# STM32_Motherboard.net
KiCad netlist of a schematic drawn in Altium Designer
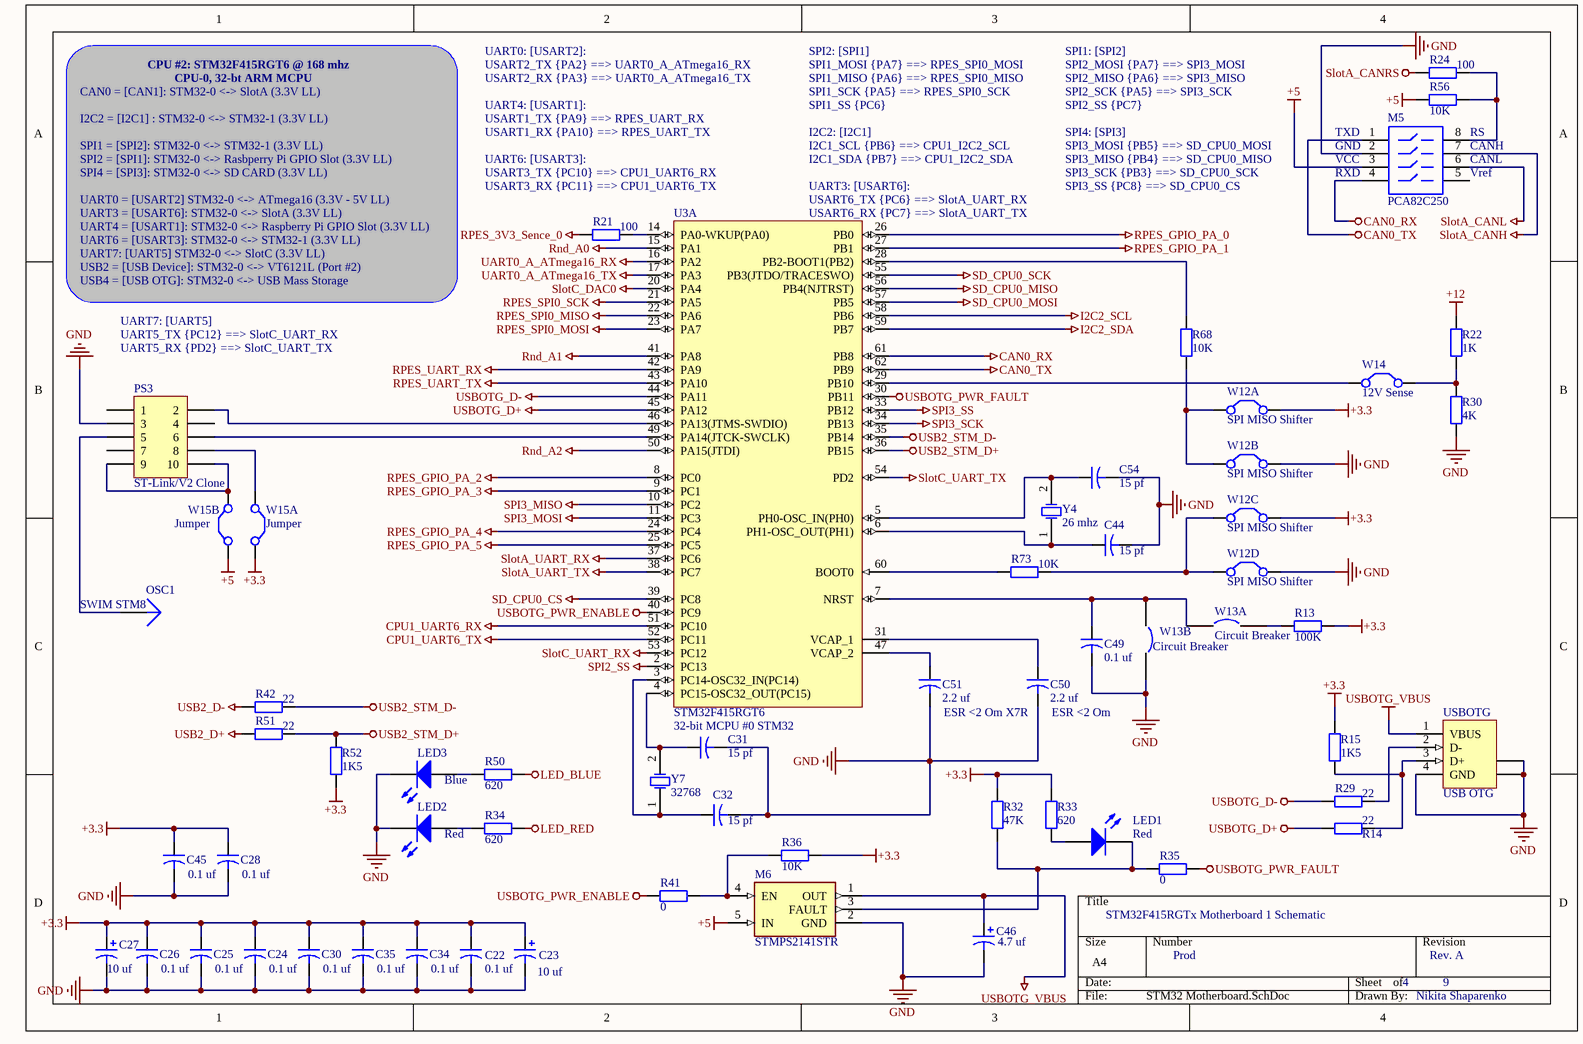
[diagram p0: STM32 Motherboard.SchDoc]

(export (version "E")
  (design (tool "Eeschema 10.0.6"))
  (components
    (comp (ref "C22")
      (value "0.1 uf")
      (footprint "CAPR5-4X5")
      (description "Capacitor")
      (fields (field (name "Comment") "Cap2") (field (name "PUBLISHER") "Altium Limited"))
      (libsource (lib "Miscellaneous Devices") (part "Cap2"))
    )
    (comp (ref "C23")
      (value "10 uf")
      (footprint "RAD-0.2")
      (description "Polarized Capacitor (Radial)")
      (fields (field (name "Comment") "Cap Pol1") (field (name "PUBLISHER") "Altium Limited"))
      (libsource (lib "Miscellaneous Devices") (part "Cap Pol1"))
    )
    (comp (ref "C24")
      (value "0.1 uf")
      (footprint "CAPR5-4X5")
      (description "Capacitor")
      (fields (field (name "Comment") "Cap2") (field (name "PUBLISHER") "Altium Limited"))
      (libsource (lib "Miscellaneous Devices") (part "Cap2"))
    )
    (comp (ref "C25")
      (value "0.1 uf")
      (footprint "CAPR5-4X5")
      (description "Capacitor")
      (fields (field (name "Comment") "Cap2") (field (name "PUBLISHER") "Altium Limited"))
      (libsource (lib "Miscellaneous Devices") (part "Cap2"))
    )
    (comp (ref "C26")
      (value "0.1 uf")
      (footprint "CAPR5-4X5")
      (description "Capacitor")
      (fields (field (name "Comment") "Cap2") (field (name "PUBLISHER") "Altium Limited"))
      (libsource (lib "Miscellaneous Devices") (part "Cap2"))
    )
    (comp (ref "C27")
      (value "10 uf")
      (footprint "RAD-0.2")
      (description "Polarized Capacitor (Radial)")
      (fields (field (name "Comment") "Cap Pol1") (field (name "PUBLISHER") "Altium Limited"))
      (libsource (lib "Miscellaneous Devices") (part "Cap Pol1"))
    )
    (comp (ref "C28")
      (value "0.1 uf")
      (footprint "CAPR5-4X5")
      (description "Capacitor")
      (fields (field (name "Comment") "Cap2") (field (name "PUBLISHER") "Altium Limited"))
      (libsource (lib "Miscellaneous Devices") (part "Cap2"))
    )
    (comp (ref "C30")
      (value "0.1 uf")
      (footprint "CAPR5-4X5")
      (description "Capacitor")
      (fields (field (name "Comment") "Cap2") (field (name "PUBLISHER") "Altium Limited"))
      (libsource (lib "Miscellaneous Devices") (part "Cap2"))
    )
    (comp (ref "C31")
      (value "15 pf")
      (footprint "CAPR5-4X5")
      (description "Capacitor")
      (fields (field (name "Comment") "Cap2") (field (name "PUBLISHER") "Altium Limited"))
      (libsource (lib "Miscellaneous Devices") (part "Cap2"))
    )
    (comp (ref "C32")
      (value "15 pf")
      (footprint "CAPR5-4X5")
      (description "Capacitor")
      (fields (field (name "Comment") "Cap2") (field (name "PUBLISHER") "Altium Limited"))
      (libsource (lib "Miscellaneous Devices") (part "Cap2"))
    )
    (comp (ref "C34")
      (value "0.1 uf")
      (footprint "CAPR5-4X5")
      (description "Capacitor")
      (fields (field (name "Comment") "Cap2") (field (name "PUBLISHER") "Altium Limited"))
      (libsource (lib "Miscellaneous Devices") (part "Cap2"))
    )
    (comp (ref "C35")
      (value "0.1 uf")
      (footprint "CAPR5-4X5")
      (description "Capacitor")
      (fields (field (name "Comment") "Cap2") (field (name "PUBLISHER") "Altium Limited"))
      (libsource (lib "Miscellaneous Devices") (part "Cap2"))
    )
    (comp (ref "C44")
      (value "15 pf")
      (footprint "CAPR5-4X5")
      (description "Capacitor")
      (fields (field (name "Comment") "Cap2") (field (name "PUBLISHER") "Altium Limited"))
      (libsource (lib "Miscellaneous Devices") (part "Cap2"))
    )
    (comp (ref "C45")
      (value "0.1 uf")
      (footprint "CAPR5-4X5")
      (description "Capacitor")
      (fields (field (name "Comment") "Cap2") (field (name "PUBLISHER") "Altium Limited"))
      (libsource (lib "Miscellaneous Devices") (part "Cap2"))
    )
    (comp (ref "C46")
      (value "4.7 uf")
      (footprint "RAD-0.2")
      (description "Polarized Capacitor (Radial)")
      (fields (field (name "Comment") "Cap Pol1") (field (name "PUBLISHER") "Altium Limited"))
      (libsource (lib "Miscellaneous Devices") (part "Cap Pol1"))
    )
    (comp (ref "C49")
      (value "0.1 uf")
      (footprint "CAPR5-4X5")
      (description "Capacitor")
      (fields (field (name "Comment") "Cap2") (field (name "PUBLISHER") "Altium Limited"))
      (libsource (lib "Miscellaneous Devices") (part "Cap2"))
    )
    (comp (ref "C50")
      (value "ESR <2 Om")
      (footprint "CAPR5-4X5")
      (description "Capacitor")
      (fields (field (name "ALTIUM_VALUE") "2.2 uf") (field (name "PUBLISHER") "Altium Limited"))
      (libsource (lib "Miscellaneous Devices") (part "Cap2"))
    )
    (comp (ref "C51")
      (value "ESR <2 Om X7R")
      (footprint "CAPR5-4X5")
      (description "Capacitor")
      (fields (field (name "ALTIUM_VALUE") "2.2 uf") (field (name "PUBLISHER") "Altium Limited"))
      (libsource (lib "Miscellaneous Devices") (part "Cap2"))
    )
    (comp (ref "C54")
      (value "15 pf")
      (footprint "CAPR5-4X5")
      (description "Capacitor")
      (fields (field (name "Comment") "Cap2") (field (name "PUBLISHER") "Altium Limited"))
      (libsource (lib "Miscellaneous Devices") (part "Cap2"))
    )
    (comp (ref "LED1")
      (value "Red")
      (footprint "LED-1")
      (description "Typical RED GaAs LED")
      (fields (field (name "PUBLISHER") "Altium Limited"))
      (libsource (lib "Miscellaneous Devices") (part "LED1"))
    )
    (comp (ref "LED2")
      (value "Red")
      (footprint "LED-1")
      (description "Typical RED GaAs LED")
      (fields (field (name "PUBLISHER") "Altium Limited"))
      (libsource (lib "Miscellaneous Devices") (part "LED1"))
    )
    (comp (ref "LED3")
      (value "Blue")
      (footprint "LED-1")
      (description "Typical RED GaAs LED")
      (fields (field (name "PUBLISHER") "Altium Limited"))
      (libsource (lib "Miscellaneous Devices") (part "LED1"))
    )
    (comp (ref "M5")
      (value "PCA82C250")
      (footprint "8S1_N")
      (description "DIP Switch")
      (fields (field (name "PUBLISHER") "Altium Limited"))
      (libsource (lib "Miscellaneous Devices") (part "SW-DIP4"))
    )
    (comp (ref "M6")
      (value "STMPS2141STR")
      (footprint "SOT95P280X145-5N")
      (description "Power Switch/Driver 1:1 N-Channel 500mA SOT-23-5")
      (fields (field (name "MF") "STMicroelectronics"))
      (libsource (lib "STMPS2141STR") (part "STMPS2141STR"))
    )
    (comp (ref "OSC1")
      (value "SWIM STM8")
      (footprint "PIN1")
      (description "Plug")
      (fields (field (name "PUBLISHER") "Altium Limited"))
      (libsource (lib "Miscellaneous Connectors") (part "Plug"))
    )
    (comp (ref "PS3")
      (value "ST-Link/V2 Clone")
      (footprint "HDR2X5")
      (description "Header, 5-Pin, Dual row")
      (fields (field (name "PUBLISHER") "Altium Limited"))
      (libsource (lib "Miscellaneous Connectors") (part "Header 5X2"))
    )
    (comp (ref "R13")
      (value "100K")
      (footprint "AXIAL-0.4")
      (description "Resistor")
      (fields (field (name "Comment") "Res2") (field (name "PUBLISHER") "Altium Limited"))
      (libsource (lib "") (part "Res2_2"))
    )
    (comp (ref "R14")
      (value "22")
      (footprint "AXIAL-0.4")
      (description "Resistor")
      (fields (field (name "Comment") "Res2") (field (name "PUBLISHER") "Altium Limited"))
      (libsource (lib "Miscellaneous Devices") (part "Res2"))
    )
    (comp (ref "R15")
      (value "1K5")
      (footprint "AXIAL-0.4")
      (description "Resistor")
      (fields (field (name "Comment") "Res2") (field (name "PUBLISHER") "Altium Limited"))
      (libsource (lib "") (part "Res2_1"))
    )
    (comp (ref "R21")
      (value "100")
      (footprint "AXIAL-0.4")
      (description "Resistor")
      (fields (field (name "Comment") "Res2") (field (name "PUBLISHER") "Altium Limited"))
      (libsource (lib "Miscellaneous Devices") (part "Res2"))
    )
    (comp (ref "R22")
      (value "1K")
      (footprint "AXIAL-0.4")
      (description "Resistor")
      (fields (field (name "Comment") "Res2") (field (name "PUBLISHER") "Altium Limited"))
      (libsource (lib "") (part "Res2_1"))
    )
    (comp (ref "R24")
      (value "100")
      (footprint "AXIAL-0.4")
      (description "Resistor")
      (fields (field (name "Comment") "Res2") (field (name "PUBLISHER") "Altium Limited"))
      (libsource (lib "Miscellaneous Devices") (part "Res2"))
    )
    (comp (ref "R29")
      (value "22")
      (footprint "AXIAL-0.4")
      (description "Resistor")
      (fields (field (name "Comment") "Res2") (field (name "PUBLISHER") "Altium Limited"))
      (libsource (lib "Miscellaneous Devices") (part "Res2"))
    )
    (comp (ref "R30")
      (value "4K")
      (footprint "AXIAL-0.4")
      (description "Resistor")
      (fields (field (name "Comment") "Res2") (field (name "PUBLISHER") "Altium Limited"))
      (libsource (lib "") (part "Res2_1"))
    )
    (comp (ref "R32")
      (value "47K")
      (footprint "AXIAL-0.4")
      (description "Resistor")
      (fields (field (name "Comment") "Res2") (field (name "PUBLISHER") "Altium Limited"))
      (libsource (lib "") (part "Res2_1"))
    )
    (comp (ref "R33")
      (value "620")
      (footprint "AXIAL-0.4")
      (description "Resistor")
      (fields (field (name "Comment") "Res2") (field (name "PUBLISHER") "Altium Limited"))
      (libsource (lib "") (part "Res2_1"))
    )
    (comp (ref "R34")
      (value "620")
      (footprint "AXIAL-0.4")
      (description "Resistor")
      (fields (field (name "Comment") "Res2") (field (name "PUBLISHER") "Altium Limited"))
      (libsource (lib "Miscellaneous Devices") (part "Res2"))
    )
    (comp (ref "R35")
      (value "0")
      (footprint "AXIAL-0.4")
      (description "Resistor")
      (fields (field (name "Comment") "Res2") (field (name "PUBLISHER") "Altium Limited"))
      (libsource (lib "Miscellaneous Devices") (part "Res2"))
    )
    (comp (ref "R36")
      (value "10K")
      (footprint "AXIAL-0.4")
      (description "Resistor")
      (fields (field (name "Comment") "Res2") (field (name "PUBLISHER") "Altium Limited"))
      (libsource (lib "") (part "Res2_2"))
    )
    (comp (ref "R41")
      (value "0")
      (footprint "AXIAL-0.4")
      (description "Resistor")
      (fields (field (name "Comment") "Res2") (field (name "PUBLISHER") "Altium Limited"))
      (libsource (lib "") (part "Res2_2"))
    )
    (comp (ref "R42")
      (value "22")
      (footprint "AXIAL-0.4")
      (description "Resistor")
      (fields (field (name "Comment") "Res2") (field (name "PUBLISHER") "Altium Limited"))
      (libsource (lib "Miscellaneous Devices") (part "Res2"))
    )
    (comp (ref "R50")
      (value "620")
      (footprint "AXIAL-0.4")
      (description "Resistor")
      (fields (field (name "Comment") "Res2") (field (name "PUBLISHER") "Altium Limited"))
      (libsource (lib "Miscellaneous Devices") (part "Res2"))
    )
    (comp (ref "R51")
      (value "22")
      (footprint "AXIAL-0.4")
      (description "Resistor")
      (fields (field (name "Comment") "Res2") (field (name "PUBLISHER") "Altium Limited"))
      (libsource (lib "Miscellaneous Devices") (part "Res2"))
    )
    (comp (ref "R52")
      (value "1K5")
      (footprint "AXIAL-0.4")
      (description "Resistor")
      (fields (field (name "Comment") "Res2") (field (name "PUBLISHER") "Altium Limited"))
      (libsource (lib "") (part "Res2_1"))
    )
    (comp (ref "R56")
      (value "10K")
      (footprint "AXIAL-0.4")
      (description "Resistor")
      (fields (field (name "Comment") "Res2") (field (name "PUBLISHER") "Altium Limited"))
      (libsource (lib "") (part "Res2_2"))
    )
    (comp (ref "R68")
      (value "10K")
      (footprint "AXIAL-0.4")
      (description "Resistor")
      (fields (field (name "Comment") "Res2") (field (name "PUBLISHER") "Altium Limited"))
      (libsource (lib "") (part "Res2_1"))
    )
    (comp (ref "R73")
      (value "10K")
      (footprint "AXIAL-0.4")
      (description "Resistor")
      (fields (field (name "Comment") "Res2") (field (name "PUBLISHER") "Altium Limited"))
      (libsource (lib "Miscellaneous Devices") (part "Res2"))
    )
    (comp (ref "U3")
      (value "STM32F415RGT6")
      (footprint "STM-LQFP64_N")
      (fields (field (name "MANUFACTURER") "STMicroelectronics"))
      (libsource (lib "STMicroelectronics STM32 F4") (part "STM32F415RGT6"))
    )
    (comp (ref "USBOTG")
      (value "USB OTG")
      (footprint "1470695A")
      (description "USB 1.1, Right Angle, SMT, A Type, Plug, 4 Position, Natural")
      (fields (field (name "PUBLISHER") "Altium Limited"))
      (libsource (lib "AMP Serial Bus USB") (part "1470695-2"))
    )
    (comp (ref "W12A")
      (value "SPI MISO Shifter")
      (footprint "RAD-0.1")
      (description "Jumper Wire")
      (fields (field (name "PUBLISHER") "Altium Limited"))
      (libsource (lib "Miscellaneous Devices") (part "Jumper"))
    )
    (comp (ref "W12B")
      (value "SPI MISO Shifter")
      (footprint "RAD-0.1")
      (description "Jumper Wire")
      (fields (field (name "PUBLISHER") "Altium Limited"))
      (libsource (lib "Miscellaneous Devices") (part "Jumper"))
    )
    (comp (ref "W12C")
      (value "SPI MISO Shifter")
      (footprint "RAD-0.1")
      (description "Jumper Wire")
      (fields (field (name "PUBLISHER") "Altium Limited"))
      (libsource (lib "Miscellaneous Devices") (part "Jumper"))
    )
    (comp (ref "W12D")
      (value "SPI MISO Shifter")
      (footprint "RAD-0.1")
      (description "Jumper Wire")
      (fields (field (name "PUBLISHER") "Altium Limited"))
      (libsource (lib "Miscellaneous Devices") (part "Jumper"))
    )
    (comp (ref "W13A")
      (value "Circuit Breaker")
      (footprint "SPST-2")
      (fields (field (name "PUBLISHER") "Altium Limited"))
      (libsource (lib "Miscellaneous Devices") (part "Circuit Breaker"))
    )
    (comp (ref "W13B")
      (value "Circuit Breaker")
      (footprint "SPST-2")
      (fields (field (name "PUBLISHER") "Altium Limited"))
      (libsource (lib "Miscellaneous Devices") (part "Circuit Breaker"))
    )
    (comp (ref "W14")
      (value "12V Sense")
      (footprint "RAD-0.1")
      (description "Jumper Wire")
      (fields (field (name "PUBLISHER") "Altium Limited"))
      (libsource (lib "Miscellaneous Devices") (part "Jumper"))
    )
    (comp (ref "W15A")
      (value "Jumper")
      (footprint "RAD-0.1")
      (description "Jumper Wire")
      (fields (field (name "PUBLISHER") "Altium Limited"))
      (libsource (lib "Miscellaneous Devices") (part "Jumper"))
    )
    (comp (ref "W15B")
      (value "Jumper")
      (footprint "RAD-0.1")
      (description "Jumper Wire")
      (fields (field (name "PUBLISHER") "Altium Limited"))
      (libsource (lib "Miscellaneous Devices") (part "Jumper"))
    )
    (comp (ref "Y4")
      (value "26 mhz")
      (footprint "R38")
      (description "Crystal Oscillator")
      (fields (field (name "PUBLISHER") "Altium Limited"))
      (libsource (lib "Miscellaneous Devices") (part "XTAL"))
    )
    (comp (ref "Y7")
      (value "32768")
      (footprint "R38")
      (description "Crystal Oscillator")
      (fields (field (name "PUBLISHER") "Altium Limited"))
      (libsource (lib "Miscellaneous Devices") (part "XTAL"))
    )
  )
  (nets
    (net (code "1") (name "+3.3") (class "Default")
      (node (ref "C22") (pin "1") (pinfunction "1_1") (pintype "passive"))
      (node (ref "C23") (pin "1") (pinfunction "1_1") (pintype "passive"))
      (node (ref "C24") (pin "1") (pinfunction "1_1") (pintype "passive"))
      (node (ref "C25") (pin "1") (pinfunction "1_1") (pintype "passive"))
      (node (ref "C26") (pin "1") (pinfunction "1_1") (pintype "passive"))
      (node (ref "C27") (pin "1") (pinfunction "1_1") (pintype "passive"))
      (node (ref "C28") (pin "1") (pinfunction "1_1") (pintype "passive"))
      (node (ref "C30") (pin "1") (pinfunction "1_1") (pintype "passive"))
      (node (ref "C34") (pin "1") (pinfunction "1_1") (pintype "passive"))
      (node (ref "C35") (pin "1") (pinfunction "1_1") (pintype "passive"))
      (node (ref "C45") (pin "1") (pinfunction "1_1") (pintype "passive"))
      (node (ref "R13") (pin "1") (pinfunction "1_1") (pintype "passive"))
      (node (ref "R15") (pin "2") (pinfunction "2_2") (pintype "passive"))
      (node (ref "R32") (pin "2") (pinfunction "2_2") (pintype "passive"))
      (node (ref "R33") (pin "2") (pinfunction "2_2") (pintype "passive"))
      (node (ref "R36") (pin "1") (pinfunction "1_1") (pintype "passive"))
      (node (ref "R52") (pin "1") (pinfunction "1_1") (pintype "passive"))
      (node (ref "W12A") (pin "2") (pinfunction "C2_2") (pintype "passive"))
      (node (ref "W12C") (pin "2") (pinfunction "C2_2") (pintype "passive"))
      (node (ref "W15A") (pin "2") (pinfunction "C2_2") (pintype "passive"))
    )
    (net (code "2") (name "+5") (class "Default")
      (node (ref "M5") (pin "3") (pinfunction "3_3") (pintype "passive"))
      (node (ref "M6") (pin "5") (pinfunction "IN_5") (pintype "input"))
      (node (ref "R56") (pin "2") (pinfunction "2_2") (pintype "passive"))
      (node (ref "W15B") (pin "1") (pinfunction "C1_1") (pintype "passive"))
    )
    (net (code "3") (name "+12") (class "Default")
      (node (ref "R22") (pin "2") (pinfunction "2_2") (pintype "passive"))
    )
    (net (code "4") (name "CAN0_RX") (class "Default")
      (node (ref "M5") (pin "4") (pinfunction "4_4") (pintype "passive"))
      (node (ref "U3") (pin "61") (pinfunction "PB8_61") (pintype "bidirectional"))
    )
    (net (code "5") (name "CAN0_TX") (class "Default")
      (node (ref "M5") (pin "1") (pinfunction "1_1") (pintype "passive"))
      (node (ref "U3") (pin "62") (pinfunction "PB9_62") (pintype "bidirectional"))
    )
    (net (code "6") (name "CPU1_UART6_RX") (class "Default")
      (node (ref "U3") (pin "51") (pinfunction "PC10_51") (pintype "bidirectional"))
    )
    (net (code "7") (name "CPU1_UART6_TX") (class "Default")
      (node (ref "U3") (pin "52") (pinfunction "PC11_52") (pintype "bidirectional"))
    )
    (net (code "8") (name "GND") (class "Default")
      (node (ref "C22") (pin "2") (pinfunction "2_2") (pintype "passive"))
      (node (ref "C23") (pin "2") (pinfunction "2_2") (pintype "passive"))
      (node (ref "C24") (pin "2") (pinfunction "2_2") (pintype "passive"))
      (node (ref "C25") (pin "2") (pinfunction "2_2") (pintype "passive"))
      (node (ref "C26") (pin "2") (pinfunction "2_2") (pintype "passive"))
      (node (ref "C27") (pin "2") (pinfunction "2_2") (pintype "passive"))
      (node (ref "C28") (pin "2") (pinfunction "2_2") (pintype "passive"))
      (node (ref "C30") (pin "2") (pinfunction "2_2") (pintype "passive"))
      (node (ref "C31") (pin "2") (pinfunction "2_2") (pintype "passive"))
      (node (ref "C32") (pin "2") (pinfunction "2_2") (pintype "passive"))
      (node (ref "C34") (pin "2") (pinfunction "2_2") (pintype "passive"))
      (node (ref "C35") (pin "2") (pinfunction "2_2") (pintype "passive"))
      (node (ref "C44") (pin "2") (pinfunction "2_2") (pintype "passive"))
      (node (ref "C45") (pin "2") (pinfunction "2_2") (pintype "passive"))
      (node (ref "C46") (pin "2") (pinfunction "2_2") (pintype "passive"))
      (node (ref "C49") (pin "2") (pinfunction "2_2") (pintype "passive"))
      (node (ref "C50") (pin "2") (pinfunction "2_2") (pintype "passive"))
      (node (ref "C51") (pin "2") (pinfunction "2_2") (pintype "passive"))
      (node (ref "C54") (pin "2") (pinfunction "2_2") (pintype "passive"))
      (node (ref "LED2") (pin "2") (pinfunction "K_2") (pintype "passive"))
      (node (ref "LED3") (pin "2") (pinfunction "K_2") (pintype "passive"))
      (node (ref "M5") (pin "2") (pinfunction "2_2") (pintype "passive"))
      (node (ref "M6") (pin "2") (pinfunction "GND_2") (pintype "power_in"))
      (node (ref "PS3") (pin "3") (pinfunction "3_3") (pintype "passive"))
      (node (ref "R30") (pin "1") (pinfunction "1_1") (pintype "passive"))
      (node (ref "USBOTG") (pin "4") (pinfunction "GND_4") (pintype "power_in"))
      (node (ref "USBOTG") (pin "5") (pinfunction "SHLD_5") (pintype "passive"))
      (node (ref "USBOTG") (pin "6") (pinfunction "SHLD_6") (pintype "passive"))
      (node (ref "W12B") (pin "2") (pinfunction "C2_2") (pintype "passive"))
      (node (ref "W12D") (pin "2") (pinfunction "C2_2") (pintype "passive"))
      (node (ref "W13B") (pin "2") (pinfunction "2_2") (pintype "passive"))
    )
    (net (code "9") (name "I2C2_SCL") (class "Default")
      (node (ref "U3") (pin "58") (pinfunction "PB6_58") (pintype "bidirectional"))
    )
    (net (code "10") (name "I2C2_SDA") (class "Default")
      (node (ref "U3") (pin "59") (pinfunction "PB7_59") (pintype "bidirectional"))
    )
    (net (code "11") (name "LED_BLUE") (class "Default")
      (node (ref "R50") (pin "2") (pinfunction "2_2") (pintype "passive"))
    )
    (net (code "12") (name "LED_RED") (class "Default")
      (node (ref "R34") (pin "2") (pinfunction "2_2") (pintype "passive"))
    )
    (net (code "13") (name "Net-(LED1-A)") (class "Default")
      (node (ref "LED1") (pin "1") (pinfunction "A_1") (pintype "passive"))
      (node (ref "R33") (pin "1") (pinfunction "1_1") (pintype "passive"))
    )
    (net (code "14") (name "Net-(LED1-K)") (class "Default")
      (node (ref "LED1") (pin "2") (pinfunction "K_2") (pintype "passive"))
      (node (ref "M6") (pin "3") (pinfunction "FAULT_3") (pintype "output"))
      (node (ref "R32") (pin "1") (pinfunction "1_1") (pintype "passive"))
      (node (ref "R35") (pin "1") (pinfunction "1_1") (pintype "passive"))
    )
    (net (code "15") (name "Net-(LED2-A)") (class "Default")
      (node (ref "LED2") (pin "1") (pinfunction "A_1") (pintype "passive"))
      (node (ref "R34") (pin "1") (pinfunction "1_1") (pintype "passive"))
    )
    (net (code "16") (name "Net-(LED3-A)") (class "Default")
      (node (ref "LED3") (pin "1") (pinfunction "A_1") (pintype "passive"))
      (node (ref "R50") (pin "1") (pinfunction "1_1") (pintype "passive"))
    )
    (net (code "17") (name "Net-(M5-Pad8)") (class "Default")
      (node (ref "M5") (pin "8") (pinfunction "8_8") (pintype "passive"))
      (node (ref "R24") (pin "2") (pinfunction "2_2") (pintype "passive"))
      (node (ref "R56") (pin "1") (pinfunction "1_1") (pintype "passive"))
    )
    (net (code "18") (name "Net-(M6-EN)") (class "Default")
      (node (ref "M6") (pin "4") (pinfunction "EN_4") (pintype "input"))
      (node (ref "R36") (pin "2") (pinfunction "2_2") (pintype "passive"))
      (node (ref "R41") (pin "1") (pinfunction "1_1") (pintype "passive"))
    )
    (net (code "19") (name "Net-(OSC1-Pad1)") (class "Default")
      (node (ref "OSC1") (pin "1") (pinfunction "1_1") (pintype "passive"))
      (node (ref "PS3") (pin "5") (pinfunction "5_5") (pintype "passive"))
    )
    (net (code "20") (name "Net-(R13-Pad2)") (class "Default")
      (node (ref "R13") (pin "2") (pinfunction "2_2") (pintype "passive"))
      (node (ref "W13A") (pin "2") (pinfunction "2_2") (pintype "passive"))
    )
    (net (code "21") (name "Net-(U3A-BOOT0)") (class "Default")
      (node (ref "R73") (pin "1") (pinfunction "1_1") (pintype "passive"))
      (node (ref "U3") (pin "60") (pinfunction "BOOT0_60") (pintype "input"))
    )
    (net (code "22") (name "Net-(U3A-NRST)") (class "Default")
      (node (ref "C49") (pin "1") (pinfunction "1_1") (pintype "passive"))
      (node (ref "U3") (pin "7") (pinfunction "NRST_7") (pintype "bidirectional"))
      (node (ref "W13A") (pin "1") (pinfunction "1_1") (pintype "passive"))
      (node (ref "W13B") (pin "1") (pinfunction "1_1") (pintype "passive"))
    )
    (net (code "23") (name "Net-(U3A-PA0-WKUP(PA0))") (class "Default")
      (node (ref "R21") (pin "2") (pinfunction "2_2") (pintype "passive"))
      (node (ref "U3") (pin "14") (pinfunction "PA0-WKUP(PA0)_14") (pintype "bidirectional"))
    )
    (net (code "24") (name "Net-(U3A-PA13(JTMS-SWDIO))") (class "Default")
      (node (ref "PS3") (pin "2") (pinfunction "2_2") (pintype "passive"))
      (node (ref "U3") (pin "46") (pinfunction "PA13(JTMS-SWDIO)_46") (pintype "bidirectional"))
    )
    (net (code "25") (name "Net-(U3A-PA14(JTCK-SWCLK))") (class "Default")
      (node (ref "PS3") (pin "6") (pinfunction "6_6") (pintype "passive"))
      (node (ref "U3") (pin "49") (pinfunction "PA14(JTCK-SWCLK)_49") (pintype "bidirectional"))
    )
    (net (code "26") (name "Net-(U3A-PB2-BOOT1(PB2))") (class "Default")
      (node (ref "R68") (pin "2") (pinfunction "2_2") (pintype "passive"))
      (node (ref "U3") (pin "28") (pinfunction "PB2-BOOT1(PB2)_28") (pintype "bidirectional"))
    )
    (net (code "27") (name "Net-(U3A-PB10)") (class "Default")
      (node (ref "U3") (pin "29") (pinfunction "PB10_29") (pintype "bidirectional"))
      (node (ref "W14") (pin "1") (pinfunction "C1_1") (pintype "passive"))
    )
    (net (code "28") (name "Net-(U3A-PC14-OSC32_IN(PC14))") (class "Default")
      (node (ref "C32") (pin "1") (pinfunction "1_1") (pintype "passive"))
      (node (ref "U3") (pin "3") (pinfunction "PC14-OSC32_IN(PC14)_3") (pintype "bidirectional"))
      (node (ref "Y7") (pin "1") (pinfunction "OSC1_1") (pintype "passive"))
    )
    (net (code "29") (name "Net-(U3A-PC15-OSC32_OUT(PC15))") (class "Default")
      (node (ref "C31") (pin "1") (pinfunction "1_1") (pintype "passive"))
      (node (ref "U3") (pin "4") (pinfunction "PC15-OSC32_OUT(PC15)_4") (pintype "bidirectional"))
      (node (ref "Y7") (pin "2") (pinfunction "OSC2_2") (pintype "passive"))
    )
    (net (code "30") (name "Net-(U3A-PH0-OSC_IN(PH0))") (class "Default")
      (node (ref "C54") (pin "1") (pinfunction "1_1") (pintype "passive"))
      (node (ref "U3") (pin "5") (pinfunction "PH0-OSC_IN(PH0)_5") (pintype "bidirectional"))
      (node (ref "Y4") (pin "2") (pinfunction "OSC2_2") (pintype "passive"))
    )
    (net (code "31") (name "Net-(U3A-PH1-OSC_OUT(PH1))") (class "Default")
      (node (ref "C44") (pin "1") (pinfunction "1_1") (pintype "passive"))
      (node (ref "U3") (pin "6") (pinfunction "PH1-OSC_OUT(PH1)_6") (pintype "bidirectional"))
      (node (ref "Y4") (pin "1") (pinfunction "OSC1_1") (pintype "passive"))
    )
    (net (code "32") (name "Net-(U3A-VCAP_1)") (class "Default")
      (node (ref "C50") (pin "1") (pinfunction "1_1") (pintype "passive"))
      (node (ref "U3") (pin "31") (pinfunction "VCAP_1_31") (pintype "power_in"))
    )
    (net (code "33") (name "Net-(U3A-VCAP_2)") (class "Default")
      (node (ref "C51") (pin "1") (pinfunction "1_1") (pintype "passive"))
      (node (ref "U3") (pin "47") (pinfunction "VCAP_2_47") (pintype "power_in"))
    )
    (net (code "34") (name "Net-(USBOTG-D+)") (class "Default")
      (node (ref "R14") (pin "2") (pinfunction "2_2") (pintype "passive"))
      (node (ref "R15") (pin "1") (pinfunction "1_1") (pintype "passive"))
      (node (ref "USBOTG") (pin "3") (pinfunction "D+_3") (pintype "input"))
    )
    (net (code "35") (name "Net-(USBOTG-D-)") (class "Default")
      (node (ref "R29") (pin "2") (pinfunction "2_2") (pintype "passive"))
      (node (ref "USBOTG") (pin "2") (pinfunction "D-_2") (pintype "input"))
    )
    (net (code "36") (name "Net-(W12A-C1)") (class "Default")
      (node (ref "R68") (pin "1") (pinfunction "1_1") (pintype "passive"))
      (node (ref "W12A") (pin "1") (pinfunction "C1_1") (pintype "passive"))
      (node (ref "W12B") (pin "1") (pinfunction "C1_1") (pintype "passive"))
    )
    (net (code "37") (name "Net-(W12C-C1)") (class "Default")
      (node (ref "R73") (pin "2") (pinfunction "2_2") (pintype "passive"))
      (node (ref "W12C") (pin "1") (pinfunction "C1_1") (pintype "passive"))
      (node (ref "W12D") (pin "1") (pinfunction "C1_1") (pintype "passive"))
    )
    (net (code "38") (name "Net-(W14-C2)") (class "Default")
      (node (ref "R22") (pin "1") (pinfunction "1_1") (pintype "passive"))
      (node (ref "R30") (pin "2") (pinfunction "2_2") (pintype "passive"))
      (node (ref "W14") (pin "2") (pinfunction "C2_2") (pintype "passive"))
    )
    (net (code "39") (name "Net-(W15A-C1)") (class "Default")
      (node (ref "PS3") (pin "8") (pinfunction "8_8") (pintype "passive"))
      (node (ref "W15A") (pin "1") (pinfunction "C1_1") (pintype "passive"))
    )
    (net (code "40") (name "Net-(W15B-C2)") (class "Default")
      (node (ref "PS3") (pin "10") (pinfunction "10_10") (pintype "passive"))
      (node (ref "PS3") (pin "9") (pinfunction "9_9") (pintype "passive"))
      (node (ref "W15B") (pin "2") (pinfunction "C2_2") (pintype "passive"))
    )
    (net (code "41") (name "RPES_3V3_Sence_0") (class "Default")
      (node (ref "R21") (pin "1") (pinfunction "1_1") (pintype "passive"))
    )
    (net (code "42") (name "RPES_GPIO_PA_0") (class "Default")
      (node (ref "U3") (pin "26") (pinfunction "PB0_26") (pintype "bidirectional"))
    )
    (net (code "43") (name "RPES_GPIO_PA_1") (class "Default")
      (node (ref "U3") (pin "27") (pinfunction "PB1_27") (pintype "bidirectional"))
    )
    (net (code "44") (name "RPES_GPIO_PA_2") (class "Default")
      (node (ref "U3") (pin "8") (pinfunction "PC0_8") (pintype "bidirectional"))
    )
    (net (code "45") (name "RPES_GPIO_PA_3") (class "Default")
      (node (ref "U3") (pin "9") (pinfunction "PC1_9") (pintype "bidirectional"))
    )
    (net (code "46") (name "RPES_GPIO_PA_4") (class "Default")
      (node (ref "U3") (pin "24") (pinfunction "PC4_24") (pintype "bidirectional"))
    )
    (net (code "47") (name "RPES_GPIO_PA_5") (class "Default")
      (node (ref "U3") (pin "25") (pinfunction "PC5_25") (pintype "bidirectional"))
    )
    (net (code "48") (name "RPES_SPI0_MISO") (class "Default")
      (node (ref "U3") (pin "22") (pinfunction "PA6_22") (pintype "bidirectional"))
    )
    (net (code "49") (name "RPES_SPI0_MOSI") (class "Default")
      (node (ref "U3") (pin "23") (pinfunction "PA7_23") (pintype "bidirectional"))
    )
    (net (code "50") (name "RPES_SPI0_SCK") (class "Default")
      (node (ref "U3") (pin "21") (pinfunction "PA5_21") (pintype "bidirectional"))
    )
    (net (code "51") (name "RPES_UART_RX") (class "Default")
      (node (ref "U3") (pin "42") (pinfunction "PA9_42") (pintype "bidirectional"))
    )
    (net (code "52") (name "RPES_UART_TX") (class "Default")
      (node (ref "U3") (pin "43") (pinfunction "PA10_43") (pintype "bidirectional"))
    )
    (net (code "53") (name "Rnd_A0") (class "Default")
      (node (ref "U3") (pin "15") (pinfunction "PA1_15") (pintype "bidirectional"))
    )
    (net (code "54") (name "Rnd_A1") (class "Default")
      (node (ref "U3") (pin "41") (pinfunction "PA8_41") (pintype "bidirectional"))
    )
    (net (code "55") (name "Rnd_A2") (class "Default")
      (node (ref "U3") (pin "50") (pinfunction "PA15(JTDI)_50") (pintype "bidirectional"))
    )
    (net (code "56") (name "SD_CPU0_CS") (class "Default")
      (node (ref "U3") (pin "39") (pinfunction "PC8_39") (pintype "bidirectional"))
    )
    (net (code "57") (name "SD_CPU0_MISO") (class "Default")
      (node (ref "U3") (pin "56") (pinfunction "PB4(NJTRST)_56") (pintype "bidirectional"))
    )
    (net (code "58") (name "SD_CPU0_MOSI") (class "Default")
      (node (ref "U3") (pin "57") (pinfunction "PB5_57") (pintype "bidirectional"))
    )
    (net (code "59") (name "SD_CPU0_SCK") (class "Default")
      (node (ref "U3") (pin "55") (pinfunction "PB3(JTDO/TRACESWO)_55") (pintype "bidirectional"))
    )
    (net (code "60") (name "SPI2_SS") (class "Default")
      (node (ref "U3") (pin "2") (pinfunction "PC13_2") (pintype "bidirectional"))
    )
    (net (code "61") (name "SPI3_MISO") (class "Default")
      (node (ref "U3") (pin "10") (pinfunction "PC2_10") (pintype "bidirectional"))
    )
    (net (code "62") (name "SPI3_MOSI") (class "Default")
      (node (ref "U3") (pin "11") (pinfunction "PC3_11") (pintype "bidirectional"))
    )
    (net (code "63") (name "SPI3_SCK") (class "Default")
      (node (ref "U3") (pin "34") (pinfunction "PB13_34") (pintype "bidirectional"))
    )
    (net (code "64") (name "SPI3_SS") (class "Default")
      (node (ref "U3") (pin "33") (pinfunction "PB12_33") (pintype "bidirectional"))
    )
    (net (code "65") (name "SlotA_CANH") (class "Default")
      (node (ref "M5") (pin "7") (pinfunction "7_7") (pintype "passive"))
    )
    (net (code "66") (name "SlotA_CANL") (class "Default")
      (node (ref "M5") (pin "6") (pinfunction "6_6") (pintype "passive"))
    )
    (net (code "67") (name "SlotA_CANRS") (class "Default")
      (node (ref "R24") (pin "1") (pinfunction "1_1") (pintype "passive"))
    )
    (net (code "68") (name "SlotA_UART_RX") (class "Default")
      (node (ref "U3") (pin "37") (pinfunction "PC6_37") (pintype "bidirectional"))
    )
    (net (code "69") (name "SlotA_UART_TX") (class "Default")
      (node (ref "U3") (pin "38") (pinfunction "PC7_38") (pintype "bidirectional"))
    )
    (net (code "70") (name "SlotC_DAC0") (class "Default")
      (node (ref "U3") (pin "20") (pinfunction "PA4_20") (pintype "bidirectional"))
    )
    (net (code "71") (name "SlotC_UART_RX") (class "Default")
      (node (ref "U3") (pin "53") (pinfunction "PC12_53") (pintype "bidirectional"))
    )
    (net (code "72") (name "SlotC_UART_TX") (class "Default")
      (node (ref "U3") (pin "54") (pinfunction "PD2_54") (pintype "bidirectional"))
    )
    (net (code "73") (name "UART0_A_ATmega16_RX") (class "Default")
      (node (ref "U3") (pin "16") (pinfunction "PA2_16") (pintype "bidirectional"))
    )
    (net (code "74") (name "UART0_A_ATmega16_TX") (class "Default")
      (node (ref "U3") (pin "17") (pinfunction "PA3_17") (pintype "bidirectional"))
    )
    (net (code "75") (name "USB2_D+") (class "Default")
      (node (ref "R51") (pin "1") (pinfunction "1_1") (pintype "passive"))
    )
    (net (code "76") (name "USB2_D-") (class "Default")
      (node (ref "R42") (pin "1") (pinfunction "1_1") (pintype "passive"))
    )
    (net (code "77") (name "USB2_STM_D+") (class "Default")
      (node (ref "R51") (pin "2") (pinfunction "2_2") (pintype "passive"))
      (node (ref "R52") (pin "2") (pinfunction "2_2") (pintype "passive"))
      (node (ref "U3") (pin "36") (pinfunction "PB15_36") (pintype "bidirectional"))
    )
    (net (code "78") (name "USB2_STM_D-") (class "Default")
      (node (ref "R42") (pin "2") (pinfunction "2_2") (pintype "passive"))
      (node (ref "U3") (pin "35") (pinfunction "PB14_35") (pintype "bidirectional"))
    )
    (net (code "79") (name "USBOTG_D+") (class "Default")
      (node (ref "R14") (pin "1") (pinfunction "1_1") (pintype "passive"))
      (node (ref "U3") (pin "45") (pinfunction "PA12_45") (pintype "bidirectional"))
    )
    (net (code "80") (name "USBOTG_D-") (class "Default")
      (node (ref "R29") (pin "1") (pinfunction "1_1") (pintype "passive"))
      (node (ref "U3") (pin "44") (pinfunction "PA11_44") (pintype "bidirectional"))
    )
    (net (code "81") (name "USBOTG_PWR_ENABLE") (class "Default")
      (node (ref "R41") (pin "2") (pinfunction "2_2") (pintype "passive"))
      (node (ref "U3") (pin "40") (pinfunction "PC9_40") (pintype "bidirectional"))
    )
    (net (code "82") (name "USBOTG_PWR_FAULT") (class "Default")
      (node (ref "R35") (pin "2") (pinfunction "2_2") (pintype "passive"))
      (node (ref "U3") (pin "30") (pinfunction "PB11_30") (pintype "bidirectional"))
    )
    (net (code "83") (name "USBOTG_VBUS") (class "Default")
      (node (ref "C46") (pin "1") (pinfunction "1_1") (pintype "passive"))
      (node (ref "M6") (pin "1") (pinfunction "OUT_1") (pintype "output"))
      (node (ref "USBOTG") (pin "1") (pinfunction "VBUS_1") (pintype "power_in"))
    )
    (net (code "84") (name "unconnected-(M5-Pad5)") (class "Default")
      (node (ref "M5") (pin "5") (pinfunction "5_5") (pintype "passive"))
    )
    (net (code "85") (name "unconnected-(PS3-Pad1)") (class "Default")
      (node (ref "PS3") (pin "1") (pinfunction "1_1") (pintype "passive"))
    )
    (net (code "86") (name "unconnected-(PS3-Pad4)") (class "Default")
      (node (ref "PS3") (pin "4") (pinfunction "4_4") (pintype "passive"))
    )
    (net (code "87") (name "unconnected-(PS3-Pad7)") (class "Default")
      (node (ref "PS3") (pin "7") (pinfunction "7_7") (pintype "passive"))
    )
  )
)
